# schematic_base_board.net
KiCad netlist of a schematic drawn in EAGLE
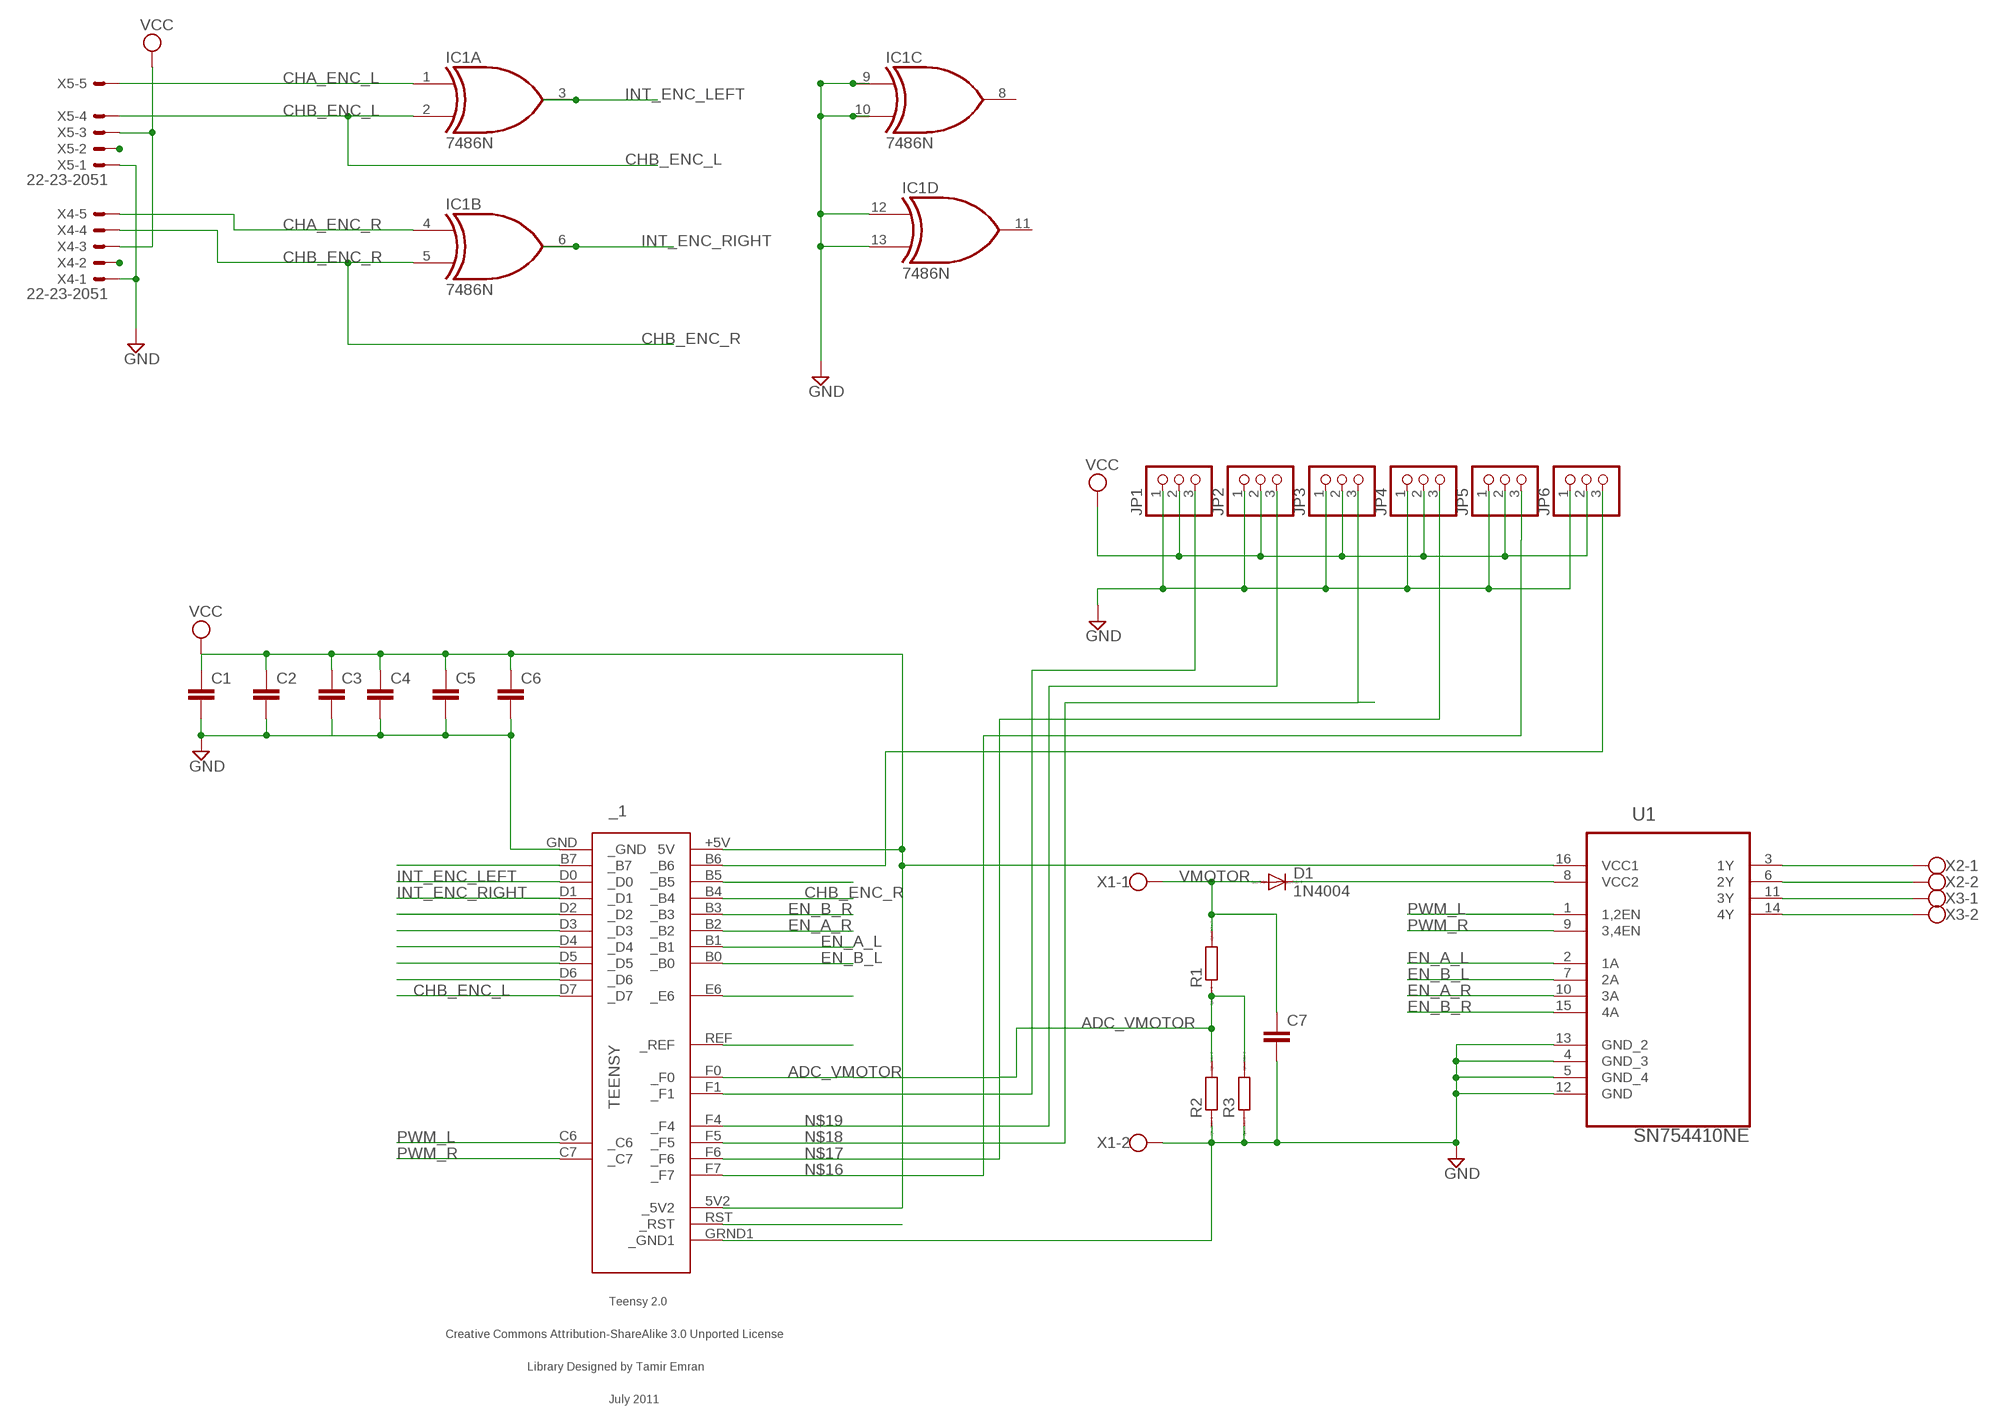
[diagram p0: schematic, sheet 1]

(export (version "E")
  (design (tool "Eeschema 10.0.6"))
  (components
    (comp (ref "C1")
      (value "C2.5/2")
      (footprint "eagle-import:C2.5-2")
      (libsource (lib "eagle-import") (part "C2.5/2"))
    )
    (comp (ref "C2")
      (value "C2.5/2")
      (footprint "eagle-import:C2.5-2")
      (libsource (lib "eagle-import") (part "C2.5/2"))
    )
    (comp (ref "C3")
      (value "C2.5/2")
      (footprint "eagle-import:C2.5-2")
      (libsource (lib "eagle-import") (part "C2.5/2"))
    )
    (comp (ref "C4")
      (value "C2.5/2")
      (footprint "eagle-import:C2.5-2")
      (libsource (lib "eagle-import") (part "C2.5/2"))
    )
    (comp (ref "C5")
      (value "C2.5/2")
      (footprint "eagle-import:C2.5-2")
      (libsource (lib "eagle-import") (part "C2.5/2"))
    )
    (comp (ref "C6")
      (value "C2.5/2")
      (footprint "eagle-import:C2.5-2")
      (libsource (lib "eagle-import") (part "C2.5/2"))
    )
    (comp (ref "C7")
      (value "C5/4.5")
      (footprint "eagle-import:C5B4.5")
      (libsource (lib "eagle-import") (part "C5/4.5"))
    )
    (comp (ref "D1")
      (value "1N4004")
      (footprint "eagle-import:DO41-10")
      (libsource (lib "eagle-import") (part "1N4004"))
    )
    (comp (ref "IC1")
      (value "7486N")
      (footprint "eagle-import:DIL14")
      (libsource (lib "eagle-import") (part "7486N"))
    )
    (comp (ref "JP1")
      (value "PINHD-1X3")
      (footprint "eagle-import:1X03")
      (libsource (lib "eagle-import") (part "PINHD-1X3"))
    )
    (comp (ref "JP2")
      (value "PINHD-1X3")
      (footprint "eagle-import:1X03")
      (libsource (lib "eagle-import") (part "PINHD-1X3"))
    )
    (comp (ref "JP3")
      (value "PINHD-1X3")
      (footprint "eagle-import:1X03")
      (libsource (lib "eagle-import") (part "PINHD-1X3"))
    )
    (comp (ref "JP4")
      (value "PINHD-1X3")
      (footprint "eagle-import:1X03")
      (libsource (lib "eagle-import") (part "PINHD-1X3"))
    )
    (comp (ref "JP5")
      (value "PINHD-1X3")
      (footprint "eagle-import:1X03")
      (libsource (lib "eagle-import") (part "PINHD-1X3"))
    )
    (comp (ref "JP6")
      (value "PINHD-1X3")
      (footprint "eagle-import:1X03")
      (libsource (lib "eagle-import") (part "PINHD-1X3"))
    )
    (comp (ref "R1")
      (value "R0207/10")
      (footprint "eagle-import:0207_10")
      (libsource (lib "eagle-import") (part "R0207/10"))
    )
    (comp (ref "R2")
      (value "R0207/10")
      (footprint "eagle-import:0207_10")
      (libsource (lib "eagle-import") (part "R0207/10"))
    )
    (comp (ref "R3")
      (value "R0207/10")
      (footprint "eagle-import:0207_10")
      (libsource (lib "eagle-import") (part "R0207/10"))
    )
    (comp (ref "U1")
      (value "SN754410NE")
      (footprint "eagle-import:DIP254P762X508-16")
      (libsource (lib "eagle-import") (part "SN754410NE"))
    )
    (comp (ref "X1")
      (value "W237-102")
      (footprint "eagle-import:W237-102")
      (fields (field (name "MPN") "237-102"))
      (libsource (lib "eagle-import") (part "W237-102"))
    )
    (comp (ref "X2")
      (value "W237-102")
      (footprint "eagle-import:W237-102")
      (fields (field (name "MPN") "237-102"))
      (libsource (lib "eagle-import") (part "W237-102"))
    )
    (comp (ref "X3")
      (value "W237-102")
      (footprint "eagle-import:W237-102")
      (fields (field (name "MPN") "237-102"))
      (libsource (lib "eagle-import") (part "W237-102"))
    )
    (comp (ref "X4")
      (value "22-23-2051")
      (footprint "eagle-import:22-23-2051")
      (fields (field (name "MF") "MOLEX"))
      (libsource (lib "eagle-import") (part "22-23-2051"))
    )
    (comp (ref "X5")
      (value "22-23-2051")
      (footprint "eagle-import:22-23-2051")
      (fields (field (name "MF") "MOLEX"))
      (libsource (lib "eagle-import") (part "22-23-2051"))
    )
    (comp (ref "_1")
      (value "TEENSY")
      (footprint "eagle-import:TEENSY")
      (libsource (lib "eagle-import") (part "TEENSY"))
    )
  )
  (nets
    (net (code "1") (name "/ADC_VMOTOR") (class "Default")
      (node (ref "R1") (pin "1") (pinfunction "1_1") (pintype "passive"))
      (node (ref "R2") (pin "2") (pinfunction "2_2") (pintype "passive"))
      (node (ref "R3") (pin "2") (pinfunction "2_2") (pintype "passive"))
      (node (ref "_1") (pin "F0") (pinfunction "_F0_F0") (pintype "bidirectional"))
    )
    (net (code "2") (name "/CHA_ENC_L") (class "Default")
      (node (ref "IC1") (pin "1") (pinfunction "I0_1") (pintype "input"))
      (node (ref "X5") (pin "5") (pinfunction "S_5") (pintype "passive"))
    )
    (net (code "3") (name "/CHA_ENC_R") (class "Default")
      (node (ref "IC1") (pin "4") (pinfunction "I0_4") (pintype "input"))
      (node (ref "X4") (pin "5") (pinfunction "S_5") (pintype "passive"))
    )
    (net (code "4") (name "/CHB_ENC_L") (class "Default")
      (node (ref "IC1") (pin "2") (pinfunction "I1_2") (pintype "input"))
      (node (ref "X5") (pin "4") (pinfunction "S_4") (pintype "passive"))
      (node (ref "_1") (pin "D7") (pinfunction "_D7_D7") (pintype "bidirectional"))
    )
    (net (code "5") (name "/CHB_ENC_R") (class "Default")
      (node (ref "IC1") (pin "5") (pinfunction "I1_5") (pintype "input"))
      (node (ref "X4") (pin "4") (pinfunction "S_4") (pintype "passive"))
      (node (ref "_1") (pin "B4") (pinfunction "_B4_B4") (pintype "bidirectional"))
    )
    (net (code "6") (name "/EN_A_L") (class "Default")
      (node (ref "U1") (pin "2") (pinfunction "1A_2") (pintype "input"))
      (node (ref "_1") (pin "B1") (pinfunction "_B1_B1") (pintype "bidirectional"))
    )
    (net (code "7") (name "/EN_A_R") (class "Default")
      (node (ref "U1") (pin "10") (pinfunction "3A_10") (pintype "input"))
      (node (ref "_1") (pin "B2") (pinfunction "_B2_B2") (pintype "bidirectional"))
    )
    (net (code "8") (name "/EN_B_L") (class "Default")
      (node (ref "U1") (pin "7") (pinfunction "2A_7") (pintype "input"))
      (node (ref "_1") (pin "B0") (pinfunction "_B0_B0") (pintype "bidirectional"))
    )
    (net (code "9") (name "/EN_B_R") (class "Default")
      (node (ref "U1") (pin "15") (pinfunction "4A_15") (pintype "input"))
      (node (ref "_1") (pin "B3") (pinfunction "_B3_B3") (pintype "bidirectional"))
    )
    (net (code "10") (name "/INT_ENC_LEFT") (class "Default")
      (node (ref "IC1") (pin "3") (pinfunction "O_3") (pintype "output"))
      (node (ref "_1") (pin "D0") (pinfunction "_D0_D0") (pintype "bidirectional"))
    )
    (net (code "11") (name "/INT_ENC_RIGHT") (class "Default")
      (node (ref "IC1") (pin "6") (pinfunction "O_6") (pintype "output"))
      (node (ref "_1") (pin "D1") (pinfunction "_D1_D1") (pintype "bidirectional"))
    )
    (net (code "12") (name "/N$16") (class "Default")
      (node (ref "JP5") (pin "3") (pinfunction "3_3") (pintype "passive"))
      (node (ref "_1") (pin "F7") (pinfunction "_F7_F7") (pintype "bidirectional"))
    )
    (net (code "13") (name "/N$17") (class "Default")
      (node (ref "JP4") (pin "3") (pinfunction "3_3") (pintype "passive"))
      (node (ref "_1") (pin "F6") (pinfunction "_F6_F6") (pintype "bidirectional"))
    )
    (net (code "14") (name "/N$18") (class "Default")
      (node (ref "JP3") (pin "3") (pinfunction "3_3") (pintype "passive"))
      (node (ref "_1") (pin "F5") (pinfunction "_F5_F5") (pintype "bidirectional"))
    )
    (net (code "15") (name "/N$19") (class "Default")
      (node (ref "JP2") (pin "3") (pinfunction "3_3") (pintype "passive"))
      (node (ref "_1") (pin "F4") (pinfunction "_F4_F4") (pintype "bidirectional"))
    )
    (net (code "16") (name "/PWM_L") (class "Default")
      (node (ref "U1") (pin "1") (pinfunction "1,2EN_1") (pintype "input"))
      (node (ref "_1") (pin "C6") (pinfunction "_C6_C6") (pintype "bidirectional"))
    )
    (net (code "17") (name "/PWM_R") (class "Default")
      (node (ref "U1") (pin "9") (pinfunction "3,4EN_9") (pintype "input"))
      (node (ref "_1") (pin "C7") (pinfunction "_C7_C7") (pintype "bidirectional"))
    )
    (net (code "18") (name "/VMOTOR") (class "Default")
      (node (ref "C7") (pin "1") (pinfunction "1_1") (pintype "passive"))
      (node (ref "D1") (pin "A") (pinfunction "A_A") (pintype "passive"))
      (node (ref "R1") (pin "2") (pinfunction "2_2") (pintype "passive"))
      (node (ref "X1") (pin "1") (pinfunction "KL_1") (pintype "passive"))
    )
    (net (code "19") (name "GND") (class "Default")
      (node (ref "C1") (pin "2") (pinfunction "2_2") (pintype "passive"))
      (node (ref "C2") (pin "2") (pinfunction "2_2") (pintype "passive"))
      (node (ref "C3") (pin "2") (pinfunction "2_2") (pintype "passive"))
      (node (ref "C4") (pin "2") (pinfunction "2_2") (pintype "passive"))
      (node (ref "C5") (pin "2") (pinfunction "2_2") (pintype "passive"))
      (node (ref "C6") (pin "2") (pinfunction "2_2") (pintype "passive"))
      (node (ref "C7") (pin "2") (pinfunction "2_2") (pintype "passive"))
      (node (ref "IC1") (pin "10") (pinfunction "I1_10") (pintype "input"))
      (node (ref "IC1") (pin "12") (pinfunction "I0_12") (pintype "input"))
      (node (ref "IC1") (pin "13") (pinfunction "I1_13") (pintype "input"))
      (node (ref "IC1") (pin "9") (pinfunction "I0_9") (pintype "input"))
      (node (ref "JP1") (pin "1") (pinfunction "1_1") (pintype "passive"))
      (node (ref "JP2") (pin "1") (pinfunction "1_1") (pintype "passive"))
      (node (ref "JP3") (pin "1") (pinfunction "1_1") (pintype "passive"))
      (node (ref "JP4") (pin "1") (pinfunction "1_1") (pintype "passive"))
      (node (ref "JP5") (pin "1") (pinfunction "1_1") (pintype "passive"))
      (node (ref "JP6") (pin "1") (pinfunction "1_1") (pintype "passive"))
      (node (ref "R2") (pin "1") (pinfunction "1_1") (pintype "passive"))
      (node (ref "R3") (pin "1") (pinfunction "1_1") (pintype "passive"))
      (node (ref "U1") (pin "12") (pinfunction "GND_12") (pintype "passive"))
      (node (ref "U1") (pin "13") (pinfunction "GND_2_13") (pintype "passive"))
      (node (ref "U1") (pin "4") (pinfunction "GND_3_4") (pintype "passive"))
      (node (ref "U1") (pin "5") (pinfunction "GND_4_5") (pintype "passive"))
      (node (ref "X1") (pin "2") (pinfunction "KL_2") (pintype "passive"))
      (node (ref "X4") (pin "1") (pinfunction "S_1") (pintype "passive"))
      (node (ref "X5") (pin "1") (pinfunction "S_1") (pintype "passive"))
      (node (ref "_1") (pin "GND") (pinfunction "_GND_GND") (pintype "bidirectional"))
      (node (ref "_1") (pin "GRND1") (pinfunction "_GND1_GRND1") (pintype "bidirectional"))
    )
    (net (code "20") (name "Net-(U1-1Y)") (class "Default")
      (node (ref "U1") (pin "3") (pinfunction "1Y_3") (pintype "output"))
      (node (ref "X2") (pin "1") (pinfunction "KL_1") (pintype "passive"))
    )
    (net (code "21") (name "Net-(U1-2Y)") (class "Default")
      (node (ref "U1") (pin "6") (pinfunction "2Y_6") (pintype "output"))
      (node (ref "X2") (pin "2") (pinfunction "KL_2") (pintype "passive"))
    )
    (net (code "22") (name "Net-(U1-3Y)") (class "Default")
      (node (ref "U1") (pin "11") (pinfunction "3Y_11") (pintype "output"))
      (node (ref "X3") (pin "1") (pinfunction "KL_1") (pintype "passive"))
    )
    (net (code "23") (name "Net-(U1-4Y)") (class "Default")
      (node (ref "U1") (pin "14") (pinfunction "4Y_14") (pintype "output"))
      (node (ref "X3") (pin "2") (pinfunction "KL_2") (pintype "passive"))
    )
    (net (code "24") (name "Net-(U1-VCC2)") (class "Default")
      (node (ref "D1") (pin "C") (pinfunction "C_C") (pintype "passive"))
      (node (ref "U1") (pin "8") (pinfunction "VCC2_8") (pintype "power_in"))
    )
    (net (code "25") (name "Net-(_1-_B6)") (class "Default")
      (node (ref "JP6") (pin "3") (pinfunction "3_3") (pintype "passive"))
      (node (ref "_1") (pin "B6") (pinfunction "_B6_B6") (pintype "bidirectional"))
    )
    (net (code "26") (name "Net-(_1-_F1)") (class "Default")
      (node (ref "JP1") (pin "3") (pinfunction "3_3") (pintype "passive"))
      (node (ref "_1") (pin "F1") (pinfunction "_F1_F1") (pintype "bidirectional"))
    )
    (net (code "27") (name "VCC") (class "Default")
      (node (ref "C1") (pin "1") (pinfunction "1_1") (pintype "passive"))
      (node (ref "C2") (pin "1") (pinfunction "1_1") (pintype "passive"))
      (node (ref "C3") (pin "1") (pinfunction "1_1") (pintype "passive"))
      (node (ref "C4") (pin "1") (pinfunction "1_1") (pintype "passive"))
      (node (ref "C5") (pin "1") (pinfunction "1_1") (pintype "passive"))
      (node (ref "C6") (pin "1") (pinfunction "1_1") (pintype "passive"))
      (node (ref "JP1") (pin "2") (pinfunction "2_2") (pintype "passive"))
      (node (ref "JP2") (pin "2") (pinfunction "2_2") (pintype "passive"))
      (node (ref "JP3") (pin "2") (pinfunction "2_2") (pintype "passive"))
      (node (ref "JP4") (pin "2") (pinfunction "2_2") (pintype "passive"))
      (node (ref "JP5") (pin "2") (pinfunction "2_2") (pintype "passive"))
      (node (ref "JP6") (pin "2") (pinfunction "2_2") (pintype "passive"))
      (node (ref "U1") (pin "16") (pinfunction "VCC1_16") (pintype "power_in"))
      (node (ref "X4") (pin "3") (pinfunction "S_3") (pintype "passive"))
      (node (ref "X5") (pin "3") (pinfunction "S_3") (pintype "passive"))
      (node (ref "_1") (pin "+5V") (pinfunction "5V_+5V") (pintype "bidirectional"))
      (node (ref "_1") (pin "5V2") (pinfunction "_5V2_5V2") (pintype "bidirectional"))
    )
    (net (code "28") (name "unconnected-(IC1C-O-Pad8)") (class "Default")
      (node (ref "IC1") (pin "8") (pinfunction "O_8") (pintype "output"))
    )
    (net (code "29") (name "unconnected-(IC1D-O-Pad11)") (class "Default")
      (node (ref "IC1") (pin "11") (pinfunction "O_11") (pintype "output"))
    )
    (net (code "30") (name "unconnected-(X4B-S-Pad2)") (class "Default")
      (node (ref "X4") (pin "2") (pinfunction "S_2") (pintype "passive"))
    )
    (net (code "31") (name "unconnected-(X5B-S-Pad2)") (class "Default")
      (node (ref "X5") (pin "2") (pinfunction "S_2") (pintype "passive"))
    )
    (net (code "32") (name "unconnected-(_1-_B5-PadB5)") (class "Default")
      (node (ref "_1") (pin "B5") (pinfunction "_B5_B5") (pintype "bidirectional"))
    )
    (net (code "33") (name "unconnected-(_1-_B7-PadB7)") (class "Default")
      (node (ref "_1") (pin "B7") (pinfunction "_B7_B7") (pintype "bidirectional"))
    )
    (net (code "34") (name "unconnected-(_1-_D2-PadD2)") (class "Default")
      (node (ref "_1") (pin "D2") (pinfunction "_D2_D2") (pintype "bidirectional"))
    )
    (net (code "35") (name "unconnected-(_1-_D3-PadD3)") (class "Default")
      (node (ref "_1") (pin "D3") (pinfunction "_D3_D3") (pintype "bidirectional"))
    )
    (net (code "36") (name "unconnected-(_1-_D4-PadD4)") (class "Default")
      (node (ref "_1") (pin "D4") (pinfunction "_D4_D4") (pintype "bidirectional"))
    )
    (net (code "37") (name "unconnected-(_1-_D5-PadD5)") (class "Default")
      (node (ref "_1") (pin "D5") (pinfunction "_D5_D5") (pintype "bidirectional"))
    )
    (net (code "38") (name "unconnected-(_1-_D6-PadD6)") (class "Default")
      (node (ref "_1") (pin "D6") (pinfunction "_D6_D6") (pintype "bidirectional"))
    )
    (net (code "39") (name "unconnected-(_1-_E6-PadE6)") (class "Default")
      (node (ref "_1") (pin "E6") (pinfunction "_E6_E6") (pintype "bidirectional"))
    )
    (net (code "40") (name "unconnected-(_1-_REF-PadREF)") (class "Default")
      (node (ref "_1") (pin "REF") (pinfunction "_REF_REF") (pintype "bidirectional"))
    )
    (net (code "41") (name "unconnected-(_1-_RST-PadRST)") (class "Default")
      (node (ref "_1") (pin "RST") (pinfunction "_RST_RST") (pintype "bidirectional"))
    )
  )
)
